# USB_OTG_FS.net
KiCad netlist of a schematic drawn in Altium Designer
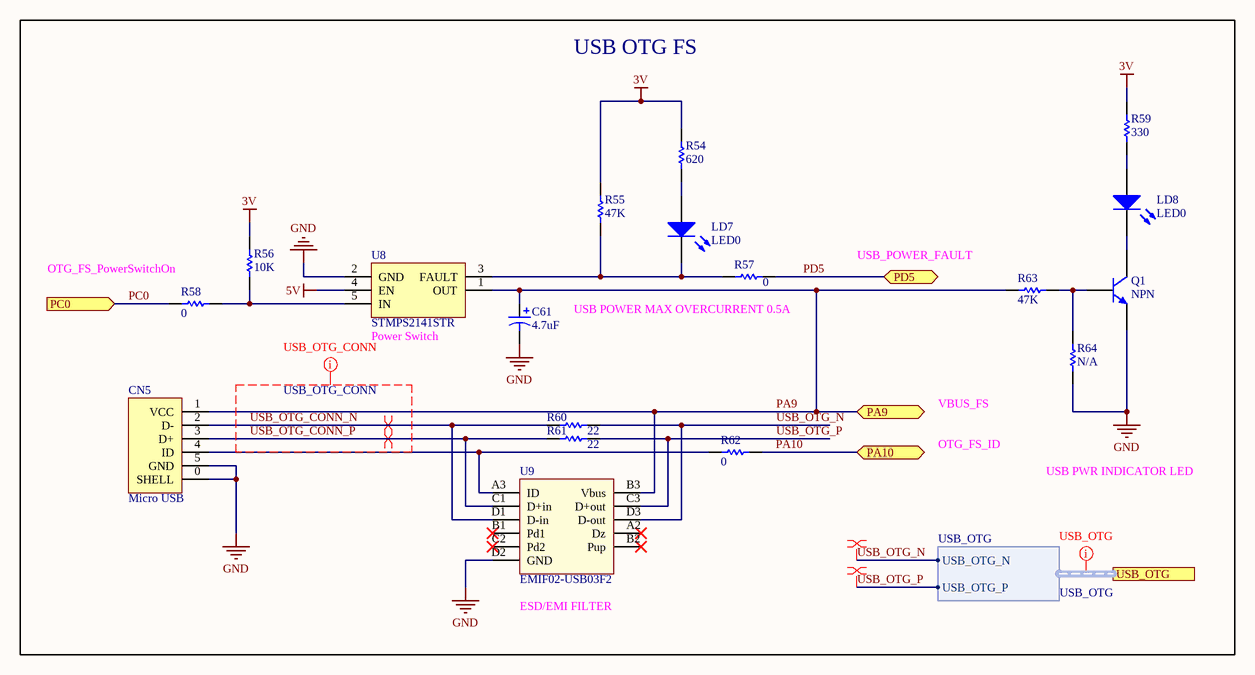
[diagram p0: USB_OTG_FS.SchDoc]

(export (version "E")
  (design (tool "Eeschema 10.0.6"))
  (components
    (comp (ref "C61")
      (value "4.7uF")
      (footprint "TANTALUM CASE A_LEVEL B")
      (description "Polarized Capacitor (Radial)")
      (fields (field (name "Comment") "Cap Pol1") (field (name "PUBLISHER") "Altium Limited"))
      (libsource (lib "STM32F4DISCOVERY") (part "Cap Pol1_1"))
    )
    (comp (ref "CN5")
      (value "Micro USB")
      (footprint "USB MICRO")
      (libsource (lib "STM32F4DISCOVERY") (part "USB MICRO"))
    )
    (comp (ref "LD7")
      (value "LED0")
      (footprint "LED_0603")
      (description "Typical INFRARED GaAs LED")
      (fields (field (name "PUBLISHER") "Altium Limited"))
      (libsource (lib "STM32F4DISCOVERY") (part "LED0"))
    )
    (comp (ref "LD8")
      (value "LED0")
      (footprint "LED_0603")
      (description "Typical INFRARED GaAs LED")
      (fields (field (name "PUBLISHER") "Altium Limited"))
      (libsource (lib "STM32F4DISCOVERY") (part "LED0"))
    )
    (comp (ref "Q1")
      (value "NPN")
      (footprint "SOT-23")
      (description "NPN Bipolar Transistor")
      (fields (field (name "PUBLISHER") "Altium Limited"))
      (libsource (lib "STM32F4DISCOVERY") (part "NPN"))
    )
    (comp (ref "R54")
      (value "620")
      (footprint "RESC0402B")
      (description "Resistor")
      (fields (field (name "Comment") "Res1") (field (name "PUBLISHER") "Altium Limited"))
      (libsource (lib "STM32F4DISCOVERY") (part "Res1_10"))
    )
    (comp (ref "R55")
      (value "47K")
      (footprint "RESC0402B")
      (description "Resistor")
      (fields (field (name "Comment") "Res1") (field (name "PUBLISHER") "Altium Limited"))
      (libsource (lib "STM32F4DISCOVERY") (part "Res1_9"))
    )
    (comp (ref "R56")
      (value "10K")
      (footprint "RESC0603B")
      (description "Resistor")
      (fields (field (name "Comment") "Res1") (field (name "PUBLISHER") "Altium Limited"))
      (libsource (lib "STM32F4DISCOVERY") (part "Res1_2"))
    )
    (comp (ref "R57")
      (value "0")
      (footprint "RESC0603B")
      (description "Resistor")
      (fields (field (name "Comment") "Res1") (field (name "PUBLISHER") "Altium Limited"))
      (libsource (lib "STM32F4DISCOVERY") (part "Res1"))
    )
    (comp (ref "R58")
      (value "0")
      (footprint "RESC0603B")
      (description "Resistor")
      (fields (field (name "Comment") "Res1") (field (name "PUBLISHER") "Altium Limited"))
      (libsource (lib "STM32F4DISCOVERY") (part "Res1"))
    )
    (comp (ref "R59")
      (value "330")
      (footprint "RESC0402B")
      (description "Resistor")
      (fields (field (name "Comment") "Res1") (field (name "PUBLISHER") "Altium Limited"))
      (libsource (lib "STM32F4DISCOVERY") (part "Res1_12"))
    )
    (comp (ref "R60")
      (value "22")
      (footprint "RESC0402B")
      (description "Resistor")
      (fields (field (name "Comment") "Res1") (field (name "PUBLISHER") "Altium Limited"))
      (libsource (lib "STM32F4DISCOVERY") (part "Res1_11"))
    )
    (comp (ref "R61")
      (value "22")
      (footprint "RESC0402B")
      (description "Resistor")
      (fields (field (name "Comment") "Res1") (field (name "PUBLISHER") "Altium Limited"))
      (libsource (lib "STM32F4DISCOVERY") (part "Res1_11"))
    )
    (comp (ref "R62")
      (value "0")
      (footprint "RESC0603B")
      (description "Resistor")
      (fields (field (name "Comment") "Res1") (field (name "PUBLISHER") "Altium Limited"))
      (libsource (lib "STM32F4DISCOVERY") (part "Res1"))
    )
    (comp (ref "R63")
      (value "47K")
      (footprint "RESC0402B")
      (description "Resistor")
      (fields (field (name "Comment") "Res1") (field (name "PUBLISHER") "Altium Limited"))
      (libsource (lib "STM32F4DISCOVERY") (part "Res1_9"))
    )
    (comp (ref "R64")
      (value "N/A")
      (footprint "RESC0402B")
      (description "Resistor")
      (fields (field (name "Comment") "Res1") (field (name "PUBLISHER") "Altium Limited"))
      (libsource (lib "STM32F4DISCOVERY") (part "Res1_13"))
    )
    (comp (ref "U8")
      (value "STMPS2141STR")
      (footprint "TSOT-23-5")
      (fields (field (name "MANUFACTURER") "STMicroelectronics"))
      (libsource (lib "STM32F4DISCOVERY") (part "STMPS2141STR"))
    )
    (comp (ref "U9")
      (value "EMIF02-USB03F2")
      (footprint "EMIF02-USB03F2")
      (fields (field (name "MANUFACTURER") "STMicroelectronics"))
      (libsource (lib "STM32F4DISCOVERY") (part "EMIF02-USB03F2"))
    )
  )
  (nets
    (net (code "2") (name "/PA9") (class "Default")
      (node (ref "C61") (pin "1") (pinfunction "1_1") (pintype "passive"))
      (node (ref "CN5") (pin "1") (pinfunction "VCC_1") (pintype "passive"))
      (node (ref "R63") (pin "2") (pinfunction "2_2") (pintype "passive"))
      (node (ref "U8") (pin "1") (pinfunction "OUT_1") (pintype "passive"))
      (node (ref "U9") (pin "B3") (pinfunction "Vbus_B3") (pintype "passive"))
    )
    (net (code "3") (name "/PA10") (class "Default")
      (node (ref "R62") (pin "2") (pinfunction "2_2") (pintype "passive"))
    )
    (net (code "4") (name "/PC0") (class "Default")
      (node (ref "R58") (pin "2") (pinfunction "2_2") (pintype "passive"))
    )
    (net (code "5") (name "/PD5") (class "Default")
      (node (ref "R57") (pin "2") (pinfunction "2_2") (pintype "passive"))
    )
    (net (code "6") (name "/USB_OTG_CONN_N") (class "Default")
      (node (ref "CN5") (pin "2") (pinfunction "D-_2") (pintype "passive"))
      (node (ref "R60") (pin "1") (pinfunction "1_1") (pintype "passive"))
      (node (ref "U9") (pin "D1") (pinfunction "D-in_D1") (pintype "passive"))
    )
    (net (code "7") (name "/USB_OTG_CONN_P") (class "Default")
      (node (ref "CN5") (pin "3") (pinfunction "D+_3") (pintype "passive"))
      (node (ref "R61") (pin "1") (pinfunction "1_1") (pintype "passive"))
      (node (ref "U9") (pin "C1") (pinfunction "D+in_C1") (pintype "passive"))
    )
    (net (code "8") (name "/USB_OTG_N") (class "Default")
      (node (ref "R60") (pin "2") (pinfunction "2_2") (pintype "passive"))
      (node (ref "U9") (pin "D3") (pinfunction "D-out_D3") (pintype "passive"))
    )
    (net (code "9") (name "/USB_OTG_P") (class "Default")
      (node (ref "R61") (pin "2") (pinfunction "2_2") (pintype "passive"))
      (node (ref "U9") (pin "C3") (pinfunction "D+out_C3") (pintype "passive"))
    )
    (net (code "11") (name "3V") (class "Default")
      (node (ref "R54") (pin "2") (pinfunction "2_2") (pintype "passive"))
      (node (ref "R55") (pin "2") (pinfunction "2_2") (pintype "passive"))
      (node (ref "R56") (pin "2") (pinfunction "2_2") (pintype "passive"))
      (node (ref "R59") (pin "2") (pinfunction "2_2") (pintype "passive"))
    )
    (net (code "12") (name "5V") (class "Default")
      (node (ref "U8") (pin "4") (pinfunction "EN_4") (pintype "passive"))
    )
    (net (code "13") (name "GND") (class "Default")
      (node (ref "C61") (pin "2") (pinfunction "2_2") (pintype "passive"))
      (node (ref "CN5") (pin "0") (pinfunction "SHELL_0") (pintype "passive"))
      (node (ref "CN5") (pin "5") (pinfunction "GND_5") (pintype "passive"))
      (node (ref "Q1") (pin "3") (pinfunction "E_3") (pintype "passive"))
      (node (ref "R64") (pin "1") (pinfunction "1_1") (pintype "passive"))
      (node (ref "U8") (pin "2") (pinfunction "GND_2") (pintype "passive"))
      (node (ref "U9") (pin "D2") (pinfunction "GND_D2") (pintype "passive"))
    )
    (net (code "14") (name "Net-(CN5-ID)") (class "Default")
      (node (ref "CN5") (pin "4") (pinfunction "ID_4") (pintype "passive"))
      (node (ref "R62") (pin "1") (pinfunction "1_1") (pintype "passive"))
      (node (ref "U9") (pin "A3") (pinfunction "ID_A3") (pintype "passive"))
    )
    (net (code "15") (name "Net-(LD7-A)") (class "Default")
      (node (ref "LD7") (pin "1") (pinfunction "A_1") (pintype "passive"))
      (node (ref "R54") (pin "1") (pinfunction "1_1") (pintype "passive"))
    )
    (net (code "16") (name "Net-(LD7-K)") (class "Default")
      (node (ref "LD7") (pin "2") (pinfunction "K_2") (pintype "passive"))
      (node (ref "R55") (pin "1") (pinfunction "1_1") (pintype "passive"))
      (node (ref "R57") (pin "1") (pinfunction "1_1") (pintype "passive"))
      (node (ref "U8") (pin "3") (pinfunction "FAULT_3") (pintype "passive"))
    )
    (net (code "17") (name "Net-(LD8-A)") (class "Default")
      (node (ref "LD8") (pin "1") (pinfunction "A_1") (pintype "passive"))
      (node (ref "R59") (pin "1") (pinfunction "1_1") (pintype "passive"))
    )
    (net (code "18") (name "Net-(LD8-K)") (class "Default")
      (node (ref "LD8") (pin "2") (pinfunction "K_2") (pintype "passive"))
      (node (ref "Q1") (pin "1") (pinfunction "C_1") (pintype "passive"))
    )
    (net (code "19") (name "Net-(Q1-B)") (class "Default")
      (node (ref "Q1") (pin "2") (pinfunction "B_2") (pintype "passive"))
      (node (ref "R63") (pin "1") (pinfunction "1_1") (pintype "passive"))
      (node (ref "R64") (pin "2") (pinfunction "2_2") (pintype "passive"))
    )
    (net (code "20") (name "Net-(U8-IN)") (class "Default")
      (node (ref "R56") (pin "1") (pinfunction "1_1") (pintype "passive"))
      (node (ref "R58") (pin "1") (pinfunction "1_1") (pintype "passive"))
      (node (ref "U8") (pin "5") (pinfunction "IN_5") (pintype "passive"))
    )
    (net (code "21") (name "unconnected-(U9-Dz-PadA2)") (class "Default")
      (node (ref "U9") (pin "A2") (pinfunction "Dz_A2") (pintype "passive+no_connect"))
    )
    (net (code "22") (name "unconnected-(U9-Pd1-PadB1)") (class "Default")
      (node (ref "U9") (pin "B1") (pinfunction "Pd1_B1") (pintype "passive+no_connect"))
    )
    (net (code "23") (name "unconnected-(U9-Pd2-PadC2)") (class "Default")
      (node (ref "U9") (pin "C2") (pinfunction "Pd2_C2") (pintype "passive+no_connect"))
    )
    (net (code "24") (name "unconnected-(U9-Pup-PadB2)") (class "Default")
      (node (ref "U9") (pin "B2") (pinfunction "Pup_B2") (pintype "passive+no_connect"))
    )
  )
)
